# Orion_CanSat_Greece.net
KiCad netlist of a schematic drawn in EAGLE
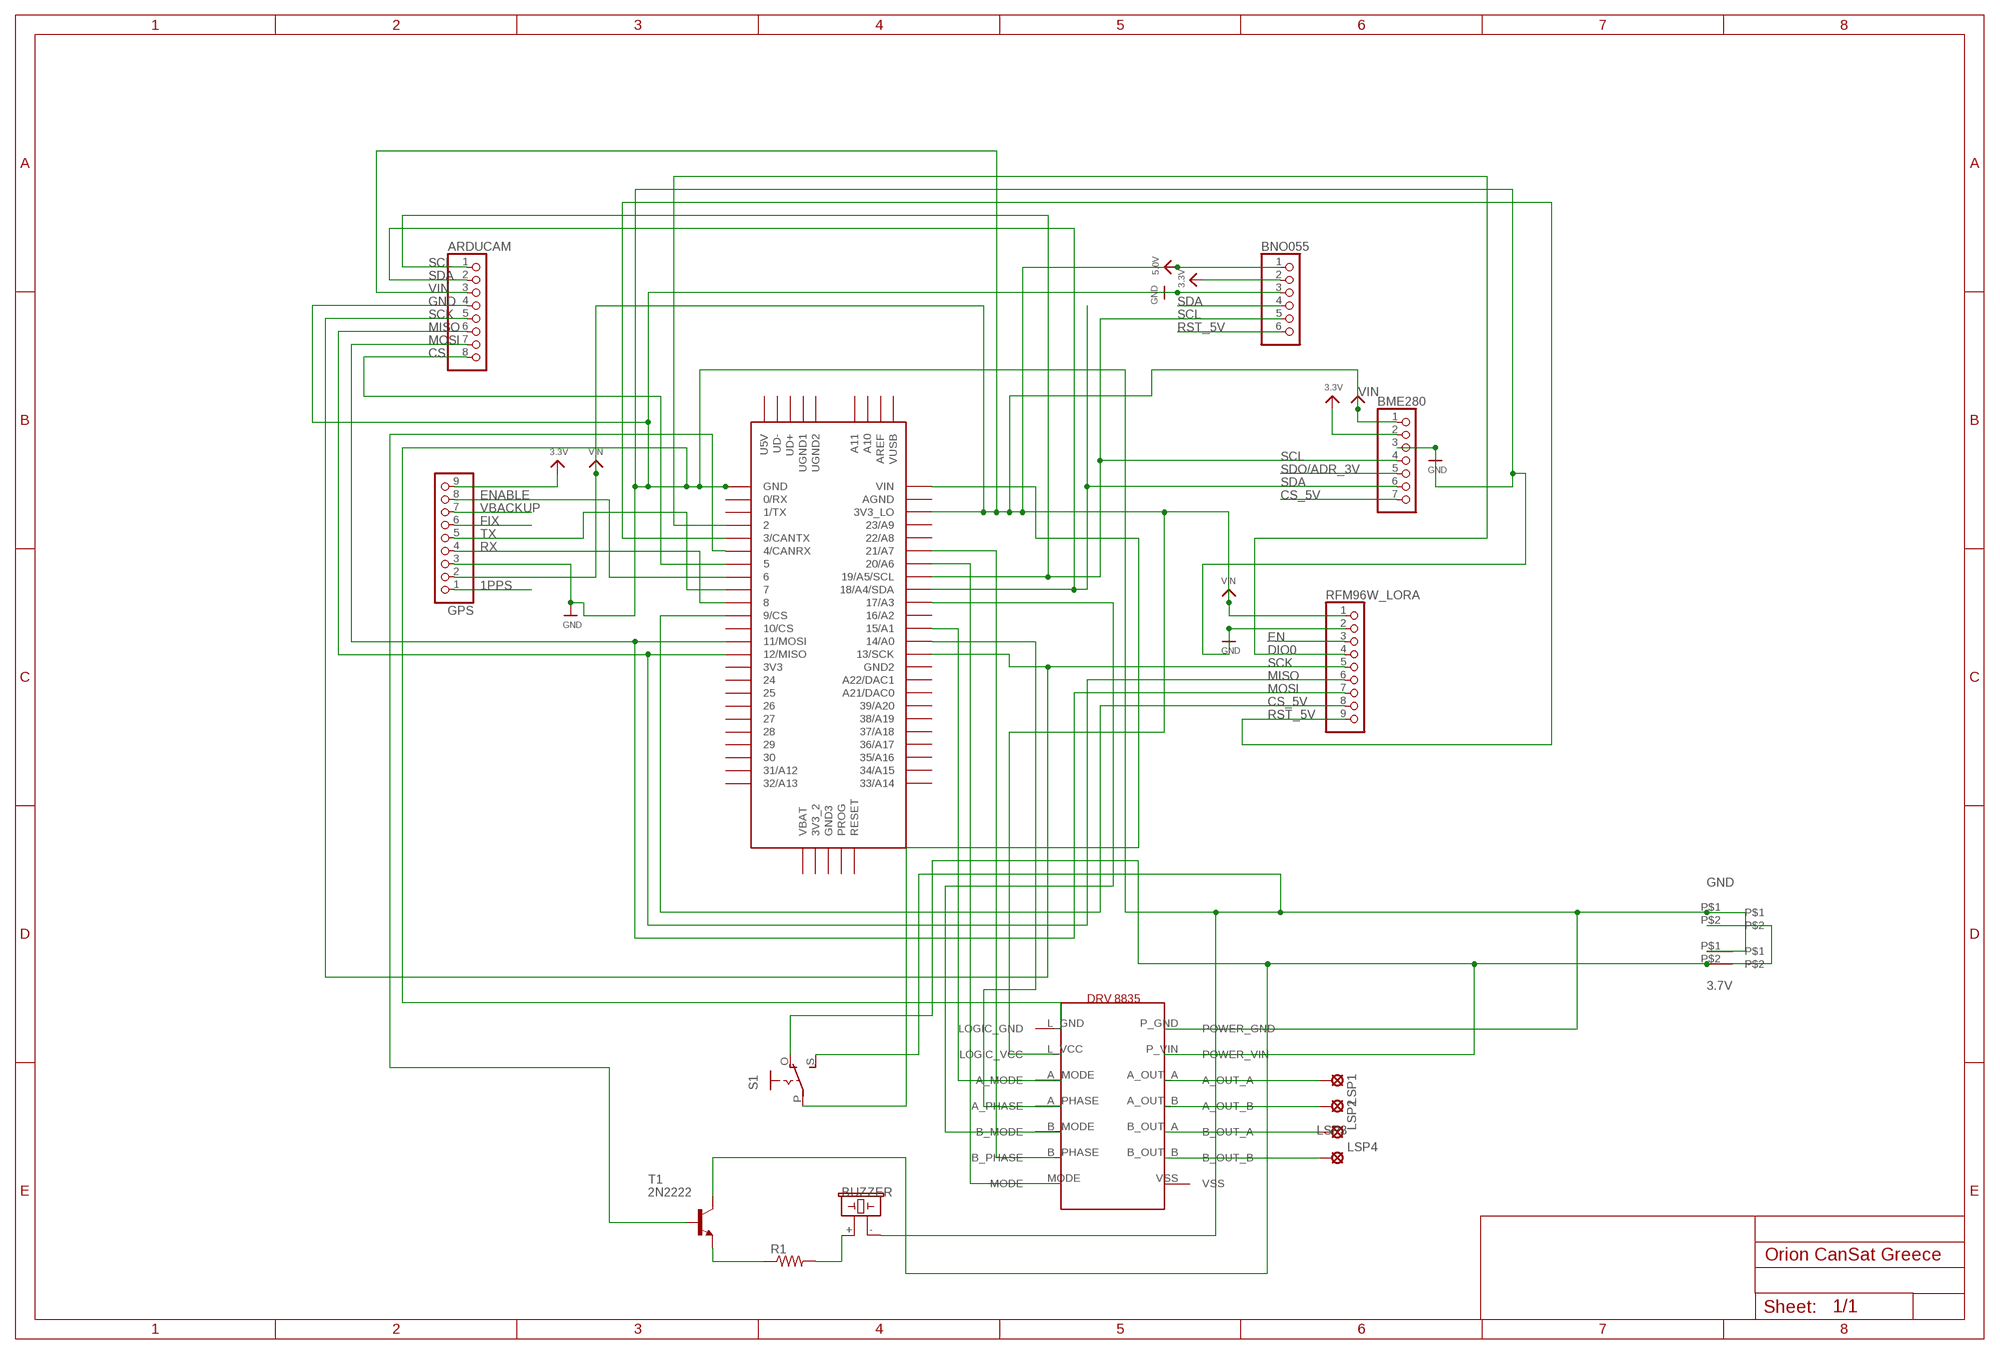
[diagram p0: schematic, sheet 1]

(export (version "E")
  (design (tool "Eeschema 10.0.6"))
  (components
    (comp (ref "ARDUCAM")
      (value "PINHD-1X8BIG")
      (footprint "eagle-import:1X08-BIG")
      (libsource (lib "eagle-import") (part "PINHD-1X8BIG"))
    )
    (comp (ref "BME280")
      (value "HEADER-1X770MIL")
      (footprint "eagle-import:1X07_ROUND_70")
      (libsource (lib "eagle-import") (part "HEADER-1X770MIL"))
    )
    (comp (ref "BNO055")
      (value "HEADER-1X676MIL")
      (footprint "eagle-import:1X06_ROUND_76")
      (libsource (lib "eagle-import") (part "HEADER-1X676MIL"))
    )
    (comp (ref "GPS")
      (value "HEADER-1X970MIL")
      (footprint "eagle-import:1X09_ROUND_70")
      (libsource (lib "eagle-import") (part "HEADER-1X970MIL"))
    )
    (comp (ref "LSP1")
      (value "LSP13")
      (footprint "eagle-import:LSP13")
      (libsource (lib "eagle-import") (part "LSP13"))
    )
    (comp (ref "LSP2")
      (value "LSP13")
      (footprint "eagle-import:LSP13")
      (libsource (lib "eagle-import") (part "LSP13"))
    )
    (comp (ref "LSP3")
      (value "LSP13")
      (footprint "eagle-import:LSP13")
      (libsource (lib "eagle-import") (part "LSP13"))
    )
    (comp (ref "LSP4")
      (value "LSP13")
      (footprint "eagle-import:LSP13")
      (libsource (lib "eagle-import") (part "LSP13"))
    )
    (comp (ref "R1")
      (value "FLIPFLOP-RES")
      (footprint "eagle-import:0805-THM")
      (libsource (lib "eagle-import") (part "FLIPFLOP-RES"))
    )
    (comp (ref "RFM96W_LORA")
      (value "HEADER-1X970MIL")
      (footprint "eagle-import:1X09_ROUND_70")
      (libsource (lib "eagle-import") (part "HEADER-1X970MIL"))
    )
    (comp (ref "S1")
      (value "EG1218S")
      (footprint "eagle-import:EG1218")
      (libsource (lib "eagle-import") (part "EG1218S"))
    )
    (comp (ref "SG2")
      (value "F/CM12P")
      (footprint "eagle-import:F_CM12P")
      (libsource (lib "eagle-import") (part "F/CM12P"))
    )
    (comp (ref "T1")
      (value "2N2222")
      (footprint "eagle-import:TO92-EBC-OVAL")
      (libsource (lib "eagle-import") (part "2N2222"))
    )
    (comp (ref "U$1")
      (value "TEENSY_3.5/3.6")
      (footprint "eagle-import:TEENSY_3.5_3.6")
      (libsource (lib "eagle-import") (part "TEENSY_3.5/3.6"))
    )
    (comp (ref "U$7")
      (value "2PINS")
      (footprint "eagle-import:2PINS")
      (libsource (lib "eagle-import") (part "2PINS"))
    )
    (comp (ref "U$8")
      (value "2PINS")
      (footprint "eagle-import:2PINS")
      (libsource (lib "eagle-import") (part "2PINS"))
    )
    (comp (ref "U$15")
      (value "DRV8835")
      (footprint "eagle-import:DRV8835")
      (libsource (lib "eagle-import") (part "DRV8835"))
    )
  )
  (nets
    (net (code "1") (name "/1PPS") (class "Default")
      (node (ref "GPS") (pin "1") (pinfunction "1_1") (pintype "passive"))
    )
    (net (code "2") (name "/CS") (class "Default")
      (node (ref "ARDUCAM") (pin "8") (pinfunction "8_8") (pintype "passive"))
      (node (ref "U$1") (pin "5") (pinfunction "5_5") (pintype "bidirectional"))
    )
    (net (code "3") (name "/CS_5V") (class "Default")
      (node (ref "BME280") (pin "7") (pinfunction "7_7") (pintype "passive"))
      (node (ref "RFM96W_LORA") (pin "8") (pinfunction "8_8") (pintype "passive"))
      (node (ref "U$1") (pin "9/CS") (pinfunction "9/CS_9/CS") (pintype "bidirectional"))
    )
    (net (code "4") (name "/DIO0") (class "Default")
      (node (ref "RFM96W_LORA") (pin "4") (pinfunction "4_4") (pintype "passive"))
      (node (ref "U$1") (pin "2") (pinfunction "2_2") (pintype "bidirectional"))
    )
    (net (code "5") (name "/EN") (class "Default")
      (node (ref "RFM96W_LORA") (pin "3") (pinfunction "3_3") (pintype "passive"))
    )
    (net (code "6") (name "/ENABLE") (class "Default")
      (node (ref "GPS") (pin "8") (pinfunction "8_8") (pintype "passive"))
      (node (ref "U$1") (pin "6") (pinfunction "6_6") (pintype "bidirectional"))
    )
    (net (code "7") (name "/FIX") (class "Default")
      (node (ref "GPS") (pin "6") (pinfunction "6_6") (pintype "passive"))
    )
    (net (code "8") (name "/MISO") (class "Default")
      (node (ref "ARDUCAM") (pin "6") (pinfunction "6_6") (pintype "passive"))
      (node (ref "RFM96W_LORA") (pin "6") (pinfunction "6_6") (pintype "passive"))
      (node (ref "U$1") (pin "12/MISO") (pinfunction "12/MISO_12/MISO") (pintype "bidirectional"))
    )
    (net (code "9") (name "/MOSI") (class "Default")
      (node (ref "ARDUCAM") (pin "7") (pinfunction "7_7") (pintype "passive"))
      (node (ref "RFM96W_LORA") (pin "7") (pinfunction "7_7") (pintype "passive"))
      (node (ref "U$1") (pin "11/MOSI") (pinfunction "11/MOSI_11/MOSI") (pintype "bidirectional"))
    )
    (net (code "10") (name "/RST_5V") (class "Default")
      (node (ref "BNO055") (pin "6") (pinfunction "6_6") (pintype "passive"))
      (node (ref "RFM96W_LORA") (pin "9") (pinfunction "9_9") (pintype "passive"))
      (node (ref "U$1") (pin "3/CANTX") (pinfunction "3/CANTX_3/CANTX") (pintype "bidirectional"))
    )
    (net (code "11") (name "/RX") (class "Default")
      (node (ref "GPS") (pin "4") (pinfunction "4_4") (pintype "passive"))
      (node (ref "U$1") (pin "8") (pinfunction "8_8") (pintype "bidirectional"))
    )
    (net (code "12") (name "/SCK") (class "Default")
      (node (ref "ARDUCAM") (pin "5") (pinfunction "5_5") (pintype "passive"))
      (node (ref "RFM96W_LORA") (pin "5") (pinfunction "5_5") (pintype "passive"))
      (node (ref "U$1") (pin "13/SCK") (pinfunction "13/SCK_13/SCK") (pintype "bidirectional"))
    )
    (net (code "13") (name "/SCL") (class "Default")
      (node (ref "ARDUCAM") (pin "1") (pinfunction "1_1") (pintype "passive"))
      (node (ref "BME280") (pin "4") (pinfunction "4_4") (pintype "passive"))
      (node (ref "BNO055") (pin "5") (pinfunction "5_5") (pintype "passive"))
      (node (ref "U$1") (pin "19/A5/SCL") (pinfunction "19/A5/SCL_19/A5/SCL") (pintype "bidirectional"))
    )
    (net (code "14") (name "/SDA") (class "Default")
      (node (ref "ARDUCAM") (pin "2") (pinfunction "2_2") (pintype "passive"))
      (node (ref "BME280") (pin "6") (pinfunction "6_6") (pintype "passive"))
      (node (ref "BNO055") (pin "4") (pinfunction "4_4") (pintype "passive"))
      (node (ref "U$1") (pin "18/A4/SDA") (pinfunction "18/A4/SDA_18/A4/SDA") (pintype "bidirectional"))
    )
    (net (code "15") (name "/SDO{slash}ADR_3V") (class "Default")
      (node (ref "BME280") (pin "5") (pinfunction "5_5") (pintype "passive"))
    )
    (net (code "16") (name "/TX") (class "Default")
      (node (ref "GPS") (pin "5") (pinfunction "5_5") (pintype "passive"))
      (node (ref "U$1") (pin "7") (pinfunction "7_7") (pintype "bidirectional"))
    )
    (net (code "17") (name "/VBACKUP") (class "Default")
      (node (ref "GPS") (pin "7") (pinfunction "7_7") (pintype "passive"))
    )
    (net (code "18") (name "3.3V") (class "Default")
      (node (ref "BME280") (pin "2") (pinfunction "2_2") (pintype "passive"))
      (node (ref "BNO055") (pin "2") (pinfunction "2_2") (pintype "passive"))
      (node (ref "GPS") (pin "9") (pinfunction "9_9") (pintype "passive"))
    )
    (net (code "19") (name "5.0V") (class "Default")
      (node (ref "ARDUCAM") (pin "3") (pinfunction "3_3") (pintype "passive"))
      (node (ref "BME280") (pin "1") (pinfunction "1_1") (pintype "passive"))
      (node (ref "BNO055") (pin "1") (pinfunction "1_1") (pintype "passive"))
      (node (ref "GPS") (pin "2") (pinfunction "2_2") (pintype "passive"))
      (node (ref "RFM96W_LORA") (pin "1") (pinfunction "1_1") (pintype "passive"))
      (node (ref "U$1") (pin "3V3_LO") (pinfunction "3V3_LO_3V3_LO") (pintype "bidirectional"))
      (node (ref "U$15") (pin "L_VCC") (pinfunction "LOGIC_VCC_L_VCC") (pintype "power_in"))
    )
    (net (code "20") (name "GND") (class "Default")
      (node (ref "ARDUCAM") (pin "4") (pinfunction "4_4") (pintype "passive"))
      (node (ref "BME280") (pin "3") (pinfunction "3_3") (pintype "passive"))
      (node (ref "BNO055") (pin "3") (pinfunction "3_3") (pintype "passive"))
      (node (ref "GPS") (pin "3") (pinfunction "3_3") (pintype "passive"))
      (node (ref "RFM96W_LORA") (pin "2") (pinfunction "2_2") (pintype "passive"))
      (node (ref "S1") (pin "S") (pinfunction "S_S") (pintype "passive"))
      (node (ref "SG2") (pin "-") (pinfunction "2_-") (pintype "passive"))
      (node (ref "U$1") (pin "GND") (pinfunction "GND_GND") (pintype "bidirectional"))
      (node (ref "U$15") (pin "L_GND") (pinfunction "LOGIC_GND_L_GND") (pintype "power_in"))
      (node (ref "U$15") (pin "P_GND") (pinfunction "POWER_GND_P_GND") (pintype "power_in"))
      (node (ref "U$7") (pin "P$1") (pinfunction "P$1_P$1") (pintype "bidirectional"))
      (node (ref "U$8") (pin "P$1") (pinfunction "P$1_P$1") (pintype "bidirectional"))
    )
    (net (code "21") (name "Net-(LSP1-PadMP)") (class "Default")
      (node (ref "LSP1") (pin "MP") (pinfunction "MP_MP") (pintype "passive"))
      (node (ref "U$15") (pin "A_OUT_A") (pinfunction "A_OUT_A_A_OUT_A") (pintype "bidirectional"))
    )
    (net (code "22") (name "Net-(LSP2-PadMP)") (class "Default")
      (node (ref "LSP2") (pin "MP") (pinfunction "MP_MP") (pintype "passive"))
      (node (ref "U$15") (pin "A_OUT_B") (pinfunction "A_OUT_B_A_OUT_B") (pintype "bidirectional"))
    )
    (net (code "23") (name "Net-(LSP3-PadMP)") (class "Default")
      (node (ref "LSP3") (pin "MP") (pinfunction "MP_MP") (pintype "passive"))
      (node (ref "U$15") (pin "B_OUT_A") (pinfunction "B_OUT_A_B_OUT_A") (pintype "bidirectional"))
    )
    (net (code "24") (name "Net-(LSP4-PadMP)") (class "Default")
      (node (ref "LSP4") (pin "MP") (pinfunction "MP_MP") (pintype "passive"))
      (node (ref "U$15") (pin "B_OUT_B") (pinfunction "B_OUT_B_B_OUT_B") (pintype "bidirectional"))
    )
    (net (code "25") (name "Net-(R1-Pad1)") (class "Default")
      (node (ref "R1") (pin "1") (pinfunction "1_1") (pintype "passive"))
      (node (ref "T1") (pin "E") (pinfunction "E_E") (pintype "passive"))
    )
    (net (code "26") (name "Net-(S1-PadP)") (class "Default")
      (node (ref "S1") (pin "P") (pinfunction "P_P") (pintype "passive"))
      (node (ref "U$1") (pin "VIN") (pinfunction "VIN_VIN") (pintype "bidirectional"))
    )
    (net (code "27") (name "Net-(SG2-1)") (class "Default")
      (node (ref "R1") (pin "2") (pinfunction "2_2") (pintype "passive"))
      (node (ref "SG2") (pin "+") (pinfunction "1_+") (pintype "passive"))
    )
    (net (code "28") (name "Net-(T1-PadB)") (class "Default")
      (node (ref "T1") (pin "B") (pinfunction "B_B") (pintype "passive"))
      (node (ref "U$1") (pin "4/CANRX") (pinfunction "4/CANRX_4/CANRX") (pintype "bidirectional"))
    )
    (net (code "29") (name "Net-(U$1-Pad14{slash}A0)") (class "Default")
      (node (ref "U$1") (pin "14/A0") (pinfunction "14/A0_14/A0") (pintype "bidirectional"))
      (node (ref "U$15") (pin "A_PHASE") (pinfunction "A_PHASE_A_PHASE") (pintype "bidirectional"))
    )
    (net (code "30") (name "Net-(U$1-Pad15{slash}A1)") (class "Default")
      (node (ref "U$1") (pin "15/A1") (pinfunction "15/A1_15/A1") (pintype "bidirectional"))
      (node (ref "U$15") (pin "A_MODE") (pinfunction "A_MODE_A_MODE") (pintype "bidirectional"))
    )
    (net (code "31") (name "Net-(U$1-Pad17{slash}A3)") (class "Default")
      (node (ref "U$1") (pin "17/A3") (pinfunction "17/A3_17/A3") (pintype "bidirectional"))
      (node (ref "U$15") (pin "B_MODE") (pinfunction "B_MODE_B_MODE") (pintype "bidirectional"))
    )
    (net (code "32") (name "Net-(U$1-Pad20{slash}A6)") (class "Default")
      (node (ref "U$1") (pin "20/A6") (pinfunction "20/A6_20/A6") (pintype "bidirectional"))
      (node (ref "U$15") (pin "MODE") (pinfunction "MODE_MODE") (pintype "bidirectional"))
    )
    (net (code "33") (name "Net-(U$1-Pad21{slash}A7)") (class "Default")
      (node (ref "U$1") (pin "21/A7") (pinfunction "21/A7_21/A7") (pintype "bidirectional"))
      (node (ref "U$15") (pin "B_PHASE") (pinfunction "B_PHASE_B_PHASE") (pintype "bidirectional"))
    )
    (net (code "34") (name "Net-(U$15-POWER_VIN)") (class "Default")
      (node (ref "S1") (pin "O") (pinfunction "O_O") (pintype "passive"))
      (node (ref "T1") (pin "C") (pinfunction "C_C") (pintype "passive"))
      (node (ref "U$15") (pin "P_VIN") (pinfunction "POWER_VIN_P_VIN") (pintype "power_in"))
      (node (ref "U$7") (pin "P$2") (pinfunction "P$2_P$2") (pintype "bidirectional"))
      (node (ref "U$8") (pin "P$2") (pinfunction "P$2_P$2") (pintype "bidirectional"))
    )
    (net (code "35") (name "unconnected-(U$1-A21{slash}DAC0-Pad21{slash}DAC0)") (class "Default")
      (node (ref "U$1") (pin "21/DAC0") (pinfunction "A21/DAC0_21/DAC0") (pintype "bidirectional"))
    )
    (net (code "36") (name "unconnected-(U$1-Pad0{slash}RX)") (class "Default")
      (node (ref "U$1") (pin "0/RX") (pinfunction "0/RX_0/RX") (pintype "bidirectional"))
    )
    (net (code "37") (name "unconnected-(U$1-Pad1{slash}TX)") (class "Default")
      (node (ref "U$1") (pin "1/TX") (pinfunction "1/TX_1/TX") (pintype "bidirectional"))
    )
    (net (code "38") (name "unconnected-(U$1-Pad3V3)") (class "Default")
      (node (ref "U$1") (pin "3V3") (pinfunction "3V3_3V3") (pintype "bidirectional"))
    )
    (net (code "39") (name "unconnected-(U$1-Pad3V3_2)") (class "Default")
      (node (ref "U$1") (pin "3V3_2") (pinfunction "3V3_2_3V3_2") (pintype "bidirectional"))
    )
    (net (code "40") (name "unconnected-(U$1-Pad10{slash}CS)") (class "Default")
      (node (ref "U$1") (pin "10/CS") (pinfunction "10/CS_10/CS") (pintype "bidirectional"))
    )
    (net (code "41") (name "unconnected-(U$1-Pad16{slash}A2)") (class "Default")
      (node (ref "U$1") (pin "16/A2") (pinfunction "16/A2_16/A2") (pintype "bidirectional"))
    )
    (net (code "42") (name "unconnected-(U$1-Pad22{slash}A8)") (class "Default")
      (node (ref "U$1") (pin "22/A8") (pinfunction "22/A8_22/A8") (pintype "bidirectional"))
    )
    (net (code "43") (name "unconnected-(U$1-Pad23{slash}A9)") (class "Default")
      (node (ref "U$1") (pin "23/A9") (pinfunction "23/A9_23/A9") (pintype "bidirectional"))
    )
    (net (code "44") (name "unconnected-(U$1-Pad24)") (class "Default")
      (node (ref "U$1") (pin "24") (pinfunction "24_24") (pintype "bidirectional"))
    )
    (net (code "45") (name "unconnected-(U$1-Pad25)") (class "Default")
      (node (ref "U$1") (pin "25") (pinfunction "25_25") (pintype "bidirectional"))
    )
    (net (code "46") (name "unconnected-(U$1-Pad26)") (class "Default")
      (node (ref "U$1") (pin "26") (pinfunction "26_26") (pintype "bidirectional"))
    )
    (net (code "47") (name "unconnected-(U$1-Pad27)") (class "Default")
      (node (ref "U$1") (pin "27") (pinfunction "27_27") (pintype "bidirectional"))
    )
    (net (code "48") (name "unconnected-(U$1-Pad28)") (class "Default")
      (node (ref "U$1") (pin "28") (pinfunction "28_28") (pintype "bidirectional"))
    )
    (net (code "49") (name "unconnected-(U$1-Pad29)") (class "Default")
      (node (ref "U$1") (pin "29") (pinfunction "29_29") (pintype "bidirectional"))
    )
    (net (code "50") (name "unconnected-(U$1-Pad30)") (class "Default")
      (node (ref "U$1") (pin "30") (pinfunction "30_30") (pintype "bidirectional"))
    )
    (net (code "51") (name "unconnected-(U$1-Pad31{slash}A12)") (class "Default")
      (node (ref "U$1") (pin "31/A12") (pinfunction "31/A12_31/A12") (pintype "bidirectional"))
    )
    (net (code "52") (name "unconnected-(U$1-Pad32{slash}A13)") (class "Default")
      (node (ref "U$1") (pin "32/A13") (pinfunction "32/A13_32/A13") (pintype "bidirectional"))
    )
    (net (code "53") (name "unconnected-(U$1-Pad33{slash}A14)") (class "Default")
      (node (ref "U$1") (pin "33/A14") (pinfunction "33/A14_33/A14") (pintype "bidirectional"))
    )
    (net (code "54") (name "unconnected-(U$1-Pad34{slash}A15)") (class "Default")
      (node (ref "U$1") (pin "34/A15") (pinfunction "34/A15_34/A15") (pintype "bidirectional"))
    )
    (net (code "55") (name "unconnected-(U$1-Pad35{slash}A16)") (class "Default")
      (node (ref "U$1") (pin "35/A16") (pinfunction "35/A16_35/A16") (pintype "bidirectional"))
    )
    (net (code "56") (name "unconnected-(U$1-Pad36{slash}A17)") (class "Default")
      (node (ref "U$1") (pin "36/A17") (pinfunction "36/A17_36/A17") (pintype "bidirectional"))
    )
    (net (code "57") (name "unconnected-(U$1-Pad37{slash}A18)") (class "Default")
      (node (ref "U$1") (pin "37/A18") (pinfunction "37/A18_37/A18") (pintype "bidirectional"))
    )
    (net (code "58") (name "unconnected-(U$1-Pad38{slash}A19)") (class "Default")
      (node (ref "U$1") (pin "38/A19") (pinfunction "38/A19_38/A19") (pintype "bidirectional"))
    )
    (net (code "59") (name "unconnected-(U$1-Pad39{slash}A20)") (class "Default")
      (node (ref "U$1") (pin "39/A20") (pinfunction "39/A20_39/A20") (pintype "bidirectional"))
    )
    (net (code "60") (name "unconnected-(U$1-PadA10)") (class "Default")
      (node (ref "U$1") (pin "A10") (pinfunction "A10_A10") (pintype "bidirectional"))
    )
    (net (code "61") (name "unconnected-(U$1-PadA11)") (class "Default")
      (node (ref "U$1") (pin "A11") (pinfunction "A11_A11") (pintype "bidirectional"))
    )
    (net (code "62") (name "unconnected-(U$1-PadA22{slash}DAC1)") (class "Default")
      (node (ref "U$1") (pin "A22/DAC1") (pinfunction "A22/DAC1_A22/DAC1") (pintype "bidirectional"))
    )
    (net (code "63") (name "unconnected-(U$1-PadAGND)") (class "Default")
      (node (ref "U$1") (pin "AGND") (pinfunction "AGND_AGND") (pintype "bidirectional"))
    )
    (net (code "64") (name "unconnected-(U$1-PadAREF)") (class "Default")
      (node (ref "U$1") (pin "AREF") (pinfunction "AREF_AREF") (pintype "bidirectional"))
    )
    (net (code "65") (name "unconnected-(U$1-PadGND2)") (class "Default")
      (node (ref "U$1") (pin "GND2") (pinfunction "GND2_GND2") (pintype "bidirectional"))
    )
    (net (code "66") (name "unconnected-(U$1-PadGND3)") (class "Default")
      (node (ref "U$1") (pin "GND3") (pinfunction "GND3_GND3") (pintype "bidirectional"))
    )
    (net (code "67") (name "unconnected-(U$1-PadPROG)") (class "Default")
      (node (ref "U$1") (pin "PROG") (pinfunction "PROG_PROG") (pintype "bidirectional"))
    )
    (net (code "68") (name "unconnected-(U$1-PadRESET)") (class "Default")
      (node (ref "U$1") (pin "RESET") (pinfunction "RESET_RESET") (pintype "bidirectional"))
    )
    (net (code "69") (name "unconnected-(U$1-PadU5V)") (class "Default")
      (node (ref "U$1") (pin "U5V") (pinfunction "U5V_U5V") (pintype "bidirectional"))
    )
    (net (code "70") (name "unconnected-(U$1-PadUD+)") (class "Default")
      (node (ref "U$1") (pin "UD+") (pinfunction "UD+_UD+") (pintype "bidirectional"))
    )
    (net (code "71") (name "unconnected-(U$1-PadUD-)") (class "Default")
      (node (ref "U$1") (pin "UD-") (pinfunction "UD-_UD-") (pintype "bidirectional"))
    )
    (net (code "72") (name "unconnected-(U$1-PadUGND1)") (class "Default")
      (node (ref "U$1") (pin "UGND1") (pinfunction "UGND1_UGND1") (pintype "bidirectional"))
    )
    (net (code "73") (name "unconnected-(U$1-PadUGND2)") (class "Default")
      (node (ref "U$1") (pin "UGND2") (pinfunction "UGND2_UGND2") (pintype "bidirectional"))
    )
    (net (code "74") (name "unconnected-(U$1-PadVBAT)") (class "Default")
      (node (ref "U$1") (pin "VBAT") (pinfunction "VBAT_VBAT") (pintype "bidirectional"))
    )
    (net (code "75") (name "unconnected-(U$1-PadVUSB)") (class "Default")
      (node (ref "U$1") (pin "VUSB") (pinfunction "VUSB_VUSB") (pintype "bidirectional"))
    )
    (net (code "76") (name "unconnected-(U$15-PadVSS)") (class "Default")
      (node (ref "U$15") (pin "VSS") (pinfunction "VSS_VSS") (pintype "bidirectional"))
    )
  )
)
